# PDB_MH.net
KiCad netlist of a schematic drawn in EAGLE
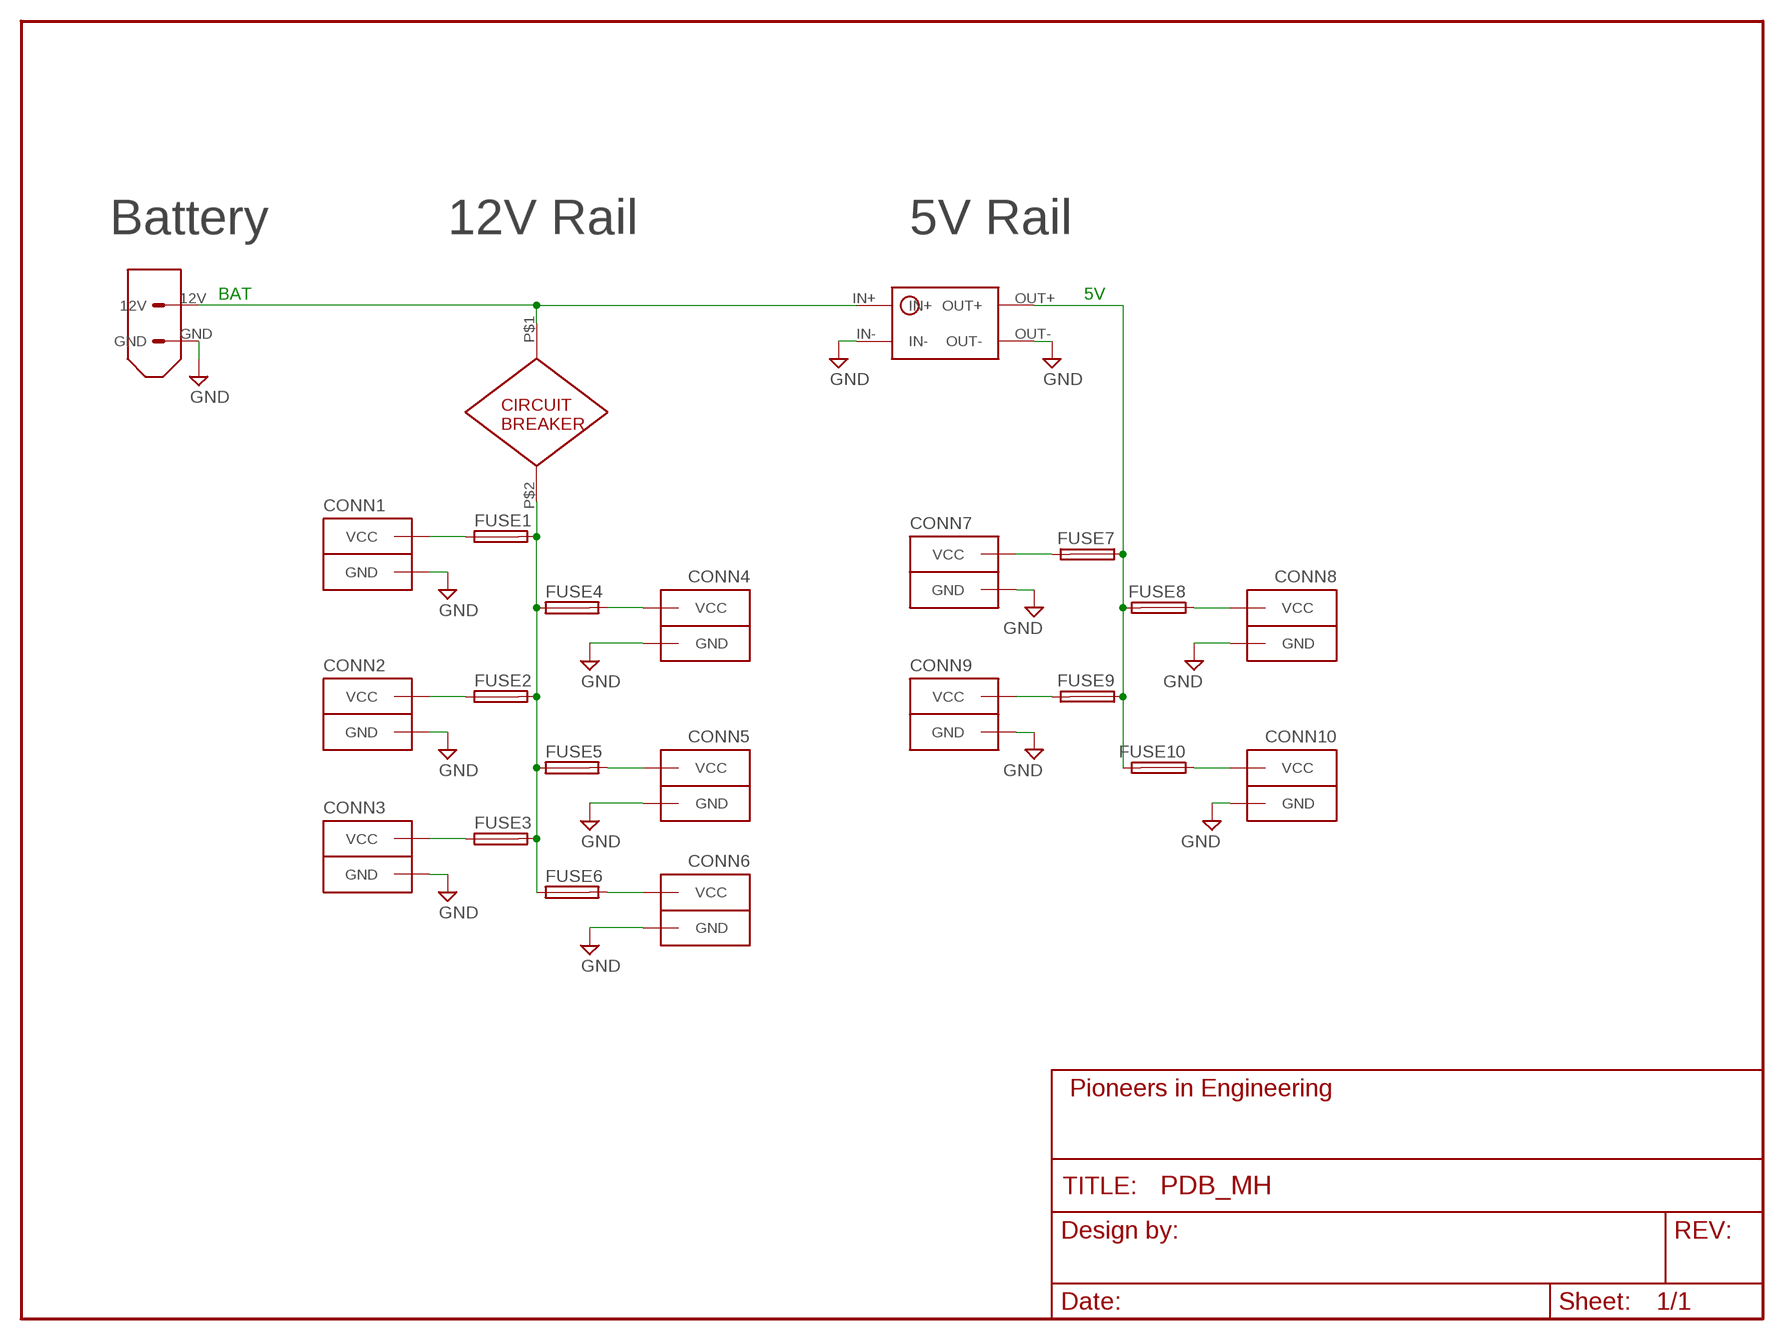
[diagram p0: schematic, sheet 1]

(export (version "E")
  (design (tool "Eeschema 10.0.6"))
  (components
    (comp (ref "CIRCUIT_BREAKER")
      (value "CIRC_BREAKER")
      (footprint "eagle-import:CIRC_BREAKER")
      (libsource (lib "eagle-import") (part "CIRC_BREAKER"))
    )
    (comp (ref "CONN1")
      (value "ANDERSONVERTICAL")
      (footprint "eagle-import:ANDERSON_VERTICAL")
      (libsource (lib "eagle-import") (part "ANDERSONVERTICAL"))
    )
    (comp (ref "CONN2")
      (value "ANDERSONVERTICAL")
      (footprint "eagle-import:ANDERSON_VERTICAL")
      (libsource (lib "eagle-import") (part "ANDERSONVERTICAL"))
    )
    (comp (ref "CONN3")
      (value "ANDERSONVERTICAL")
      (footprint "eagle-import:ANDERSON_VERTICAL")
      (libsource (lib "eagle-import") (part "ANDERSONVERTICAL"))
    )
    (comp (ref "CONN4")
      (value "ANDERSONVERTICAL")
      (footprint "eagle-import:ANDERSON_VERTICAL")
      (libsource (lib "eagle-import") (part "ANDERSONVERTICAL"))
    )
    (comp (ref "CONN5")
      (value "ANDERSONVERTICAL")
      (footprint "eagle-import:ANDERSON_VERTICAL")
      (libsource (lib "eagle-import") (part "ANDERSONVERTICAL"))
    )
    (comp (ref "CONN6")
      (value "ANDERSONVERTICAL")
      (footprint "eagle-import:ANDERSON_VERTICAL")
      (libsource (lib "eagle-import") (part "ANDERSONVERTICAL"))
    )
    (comp (ref "CONN7")
      (value "ANDERSONVERTICAL")
      (footprint "eagle-import:ANDERSON_VERTICAL")
      (libsource (lib "eagle-import") (part "ANDERSONVERTICAL"))
    )
    (comp (ref "CONN8")
      (value "ANDERSONVERTICAL")
      (footprint "eagle-import:ANDERSON_VERTICAL")
      (libsource (lib "eagle-import") (part "ANDERSONVERTICAL"))
    )
    (comp (ref "CONN9")
      (value "ANDERSONVERTICAL")
      (footprint "eagle-import:ANDERSON_VERTICAL")
      (libsource (lib "eagle-import") (part "ANDERSONVERTICAL"))
    )
    (comp (ref "CONN10")
      (value "ANDERSONVERTICAL")
      (footprint "eagle-import:ANDERSON_VERTICAL")
      (libsource (lib "eagle-import") (part "ANDERSONVERTICAL"))
    )
    (comp (ref "FUSE1")
      (value "FUSE_HOLDER_SMD")
      (footprint "eagle-import:FUSE_HOLDER_SMD")
      (libsource (lib "eagle-import") (part "FUSE_HOLDER_SMD"))
    )
    (comp (ref "FUSE2")
      (value "FUSE_HOLDER_SMD")
      (footprint "eagle-import:FUSE_HOLDER_SMD")
      (libsource (lib "eagle-import") (part "FUSE_HOLDER_SMD"))
    )
    (comp (ref "FUSE3")
      (value "FUSE_HOLDER_SMD")
      (footprint "eagle-import:FUSE_HOLDER_SMD")
      (libsource (lib "eagle-import") (part "FUSE_HOLDER_SMD"))
    )
    (comp (ref "FUSE4")
      (value "FUSE_HOLDER_SMD")
      (footprint "eagle-import:FUSE_HOLDER_SMD")
      (libsource (lib "eagle-import") (part "FUSE_HOLDER_SMD"))
    )
    (comp (ref "FUSE5")
      (value "FUSE_HOLDER_SMD")
      (footprint "eagle-import:FUSE_HOLDER_SMD")
      (libsource (lib "eagle-import") (part "FUSE_HOLDER_SMD"))
    )
    (comp (ref "FUSE6")
      (value "FUSE_HOLDER_SMD")
      (footprint "eagle-import:FUSE_HOLDER_SMD")
      (libsource (lib "eagle-import") (part "FUSE_HOLDER_SMD"))
    )
    (comp (ref "FUSE7")
      (value "FUSE_HOLDER_SMD")
      (footprint "eagle-import:FUSE_HOLDER_SMD")
      (libsource (lib "eagle-import") (part "FUSE_HOLDER_SMD"))
    )
    (comp (ref "FUSE8")
      (value "FUSE_HOLDER_SMD")
      (footprint "eagle-import:FUSE_HOLDER_SMD")
      (libsource (lib "eagle-import") (part "FUSE_HOLDER_SMD"))
    )
    (comp (ref "FUSE9")
      (value "FUSE_HOLDER_SMD")
      (footprint "eagle-import:FUSE_HOLDER_SMD")
      (libsource (lib "eagle-import") (part "FUSE_HOLDER_SMD"))
    )
    (comp (ref "FUSE10")
      (value "FUSE_HOLDER_SMD")
      (footprint "eagle-import:FUSE_HOLDER_SMD")
      (libsource (lib "eagle-import") (part "FUSE_HOLDER_SMD"))
    )
    (comp (ref "U$1")
      (value "XT60CONNECTOR")
      (footprint "eagle-import:XT60CONNECTOR")
      (fields (field (name "PARTNUMBER") "PRT-10474 "))
      (libsource (lib "eagle-import") (part "XT60CONNECTOR"))
    )
    (comp (ref "U$7")
      (value "BUCK_CONVERTER_5V")
      (footprint "eagle-import:BUCK_CONVERTER_5V")
      (libsource (lib "eagle-import") (part "BUCK_CONVERTER_5V"))
    )
  )
  (nets
    (net (code "1") (name "/5V") (class "Default")
      (node (ref "FUSE10") (pin "P$2_DOWN") (pinfunction "2_P$2_DOWN") (pintype "passive"))
      (node (ref "FUSE10") (pin "P$2_UP") (pinfunction "2_P$2_UP") (pintype "passive"))
      (node (ref "FUSE7") (pin "P$1_DOWN") (pinfunction "1_P$1_DOWN") (pintype "passive"))
      (node (ref "FUSE7") (pin "P$1_UP") (pinfunction "1_P$1_UP") (pintype "passive"))
      (node (ref "FUSE8") (pin "P$2_DOWN") (pinfunction "2_P$2_DOWN") (pintype "passive"))
      (node (ref "FUSE8") (pin "P$2_UP") (pinfunction "2_P$2_UP") (pintype "passive"))
      (node (ref "FUSE9") (pin "P$1_DOWN") (pinfunction "1_P$1_DOWN") (pintype "passive"))
      (node (ref "FUSE9") (pin "P$1_UP") (pinfunction "1_P$1_UP") (pintype "passive"))
      (node (ref "U$7") (pin "OUT+") (pinfunction "OUT+_OUT+") (pintype "bidirectional"))
    )
    (net (code "2") (name "/BAT") (class "Default")
      (node (ref "CIRCUIT_BREAKER") (pin "P$1") (pinfunction "P$1_P$1") (pintype "bidirectional"))
      (node (ref "U$1") (pin "12V") (pinfunction "12V_12V") (pintype "bidirectional"))
      (node (ref "U$7") (pin "IN+") (pinfunction "IN+_IN+") (pintype "bidirectional"))
    )
    (net (code "3") (name "GND") (class "Default")
      (node (ref "CONN1") (pin "PIN1") (pinfunction "GND_PIN1") (pintype "bidirectional"))
      (node (ref "CONN10") (pin "PIN1") (pinfunction "GND_PIN1") (pintype "bidirectional"))
      (node (ref "CONN2") (pin "PIN1") (pinfunction "GND_PIN1") (pintype "bidirectional"))
      (node (ref "CONN3") (pin "PIN1") (pinfunction "GND_PIN1") (pintype "bidirectional"))
      (node (ref "CONN4") (pin "PIN1") (pinfunction "GND_PIN1") (pintype "bidirectional"))
      (node (ref "CONN5") (pin "PIN1") (pinfunction "GND_PIN1") (pintype "bidirectional"))
      (node (ref "CONN6") (pin "PIN1") (pinfunction "GND_PIN1") (pintype "bidirectional"))
      (node (ref "CONN7") (pin "PIN1") (pinfunction "GND_PIN1") (pintype "bidirectional"))
      (node (ref "CONN8") (pin "PIN1") (pinfunction "GND_PIN1") (pintype "bidirectional"))
      (node (ref "CONN9") (pin "PIN1") (pinfunction "GND_PIN1") (pintype "bidirectional"))
      (node (ref "U$1") (pin "GND") (pinfunction "GND_GND") (pintype "bidirectional"))
      (node (ref "U$7") (pin "IN-") (pinfunction "IN-_IN-") (pintype "bidirectional"))
      (node (ref "U$7") (pin "OUT-") (pinfunction "OUT-_OUT-") (pintype "bidirectional"))
    )
    (net (code "4") (name "Net-(CIRCUIT_BREAKER-PadP$2)") (class "Default")
      (node (ref "CIRCUIT_BREAKER") (pin "P$2") (pinfunction "P$2_P$2") (pintype "bidirectional"))
      (node (ref "FUSE1") (pin "P$2_DOWN") (pinfunction "2_P$2_DOWN") (pintype "passive"))
      (node (ref "FUSE1") (pin "P$2_UP") (pinfunction "2_P$2_UP") (pintype "passive"))
      (node (ref "FUSE2") (pin "P$2_DOWN") (pinfunction "2_P$2_DOWN") (pintype "passive"))
      (node (ref "FUSE2") (pin "P$2_UP") (pinfunction "2_P$2_UP") (pintype "passive"))
      (node (ref "FUSE3") (pin "P$2_DOWN") (pinfunction "2_P$2_DOWN") (pintype "passive"))
      (node (ref "FUSE3") (pin "P$2_UP") (pinfunction "2_P$2_UP") (pintype "passive"))
      (node (ref "FUSE4") (pin "P$1_DOWN") (pinfunction "1_P$1_DOWN") (pintype "passive"))
      (node (ref "FUSE4") (pin "P$1_UP") (pinfunction "1_P$1_UP") (pintype "passive"))
      (node (ref "FUSE5") (pin "P$1_DOWN") (pinfunction "1_P$1_DOWN") (pintype "passive"))
      (node (ref "FUSE5") (pin "P$1_UP") (pinfunction "1_P$1_UP") (pintype "passive"))
      (node (ref "FUSE6") (pin "P$1_DOWN") (pinfunction "1_P$1_DOWN") (pintype "passive"))
      (node (ref "FUSE6") (pin "P$1_UP") (pinfunction "1_P$1_UP") (pintype "passive"))
    )
    (net (code "5") (name "Net-(CONN1-VCC)") (class "Default")
      (node (ref "CONN1") (pin "PIN2") (pinfunction "VCC_PIN2") (pintype "bidirectional"))
      (node (ref "FUSE1") (pin "P$1_DOWN") (pinfunction "1_P$1_DOWN") (pintype "passive"))
      (node (ref "FUSE1") (pin "P$1_UP") (pinfunction "1_P$1_UP") (pintype "passive"))
    )
    (net (code "6") (name "Net-(CONN2-VCC)") (class "Default")
      (node (ref "CONN2") (pin "PIN2") (pinfunction "VCC_PIN2") (pintype "bidirectional"))
      (node (ref "FUSE2") (pin "P$1_DOWN") (pinfunction "1_P$1_DOWN") (pintype "passive"))
      (node (ref "FUSE2") (pin "P$1_UP") (pinfunction "1_P$1_UP") (pintype "passive"))
    )
    (net (code "7") (name "Net-(CONN3-VCC)") (class "Default")
      (node (ref "CONN3") (pin "PIN2") (pinfunction "VCC_PIN2") (pintype "bidirectional"))
      (node (ref "FUSE3") (pin "P$1_DOWN") (pinfunction "1_P$1_DOWN") (pintype "passive"))
      (node (ref "FUSE3") (pin "P$1_UP") (pinfunction "1_P$1_UP") (pintype "passive"))
    )
    (net (code "8") (name "Net-(CONN4-VCC)") (class "Default")
      (node (ref "CONN4") (pin "PIN2") (pinfunction "VCC_PIN2") (pintype "bidirectional"))
      (node (ref "FUSE4") (pin "P$2_DOWN") (pinfunction "2_P$2_DOWN") (pintype "passive"))
      (node (ref "FUSE4") (pin "P$2_UP") (pinfunction "2_P$2_UP") (pintype "passive"))
    )
    (net (code "9") (name "Net-(CONN5-VCC)") (class "Default")
      (node (ref "CONN5") (pin "PIN2") (pinfunction "VCC_PIN2") (pintype "bidirectional"))
      (node (ref "FUSE5") (pin "P$2_DOWN") (pinfunction "2_P$2_DOWN") (pintype "passive"))
      (node (ref "FUSE5") (pin "P$2_UP") (pinfunction "2_P$2_UP") (pintype "passive"))
    )
    (net (code "10") (name "Net-(CONN6-VCC)") (class "Default")
      (node (ref "CONN6") (pin "PIN2") (pinfunction "VCC_PIN2") (pintype "bidirectional"))
      (node (ref "FUSE6") (pin "P$2_DOWN") (pinfunction "2_P$2_DOWN") (pintype "passive"))
      (node (ref "FUSE6") (pin "P$2_UP") (pinfunction "2_P$2_UP") (pintype "passive"))
    )
    (net (code "11") (name "Net-(CONN7-VCC)") (class "Default")
      (node (ref "CONN7") (pin "PIN2") (pinfunction "VCC_PIN2") (pintype "bidirectional"))
      (node (ref "FUSE7") (pin "P$2_DOWN") (pinfunction "2_P$2_DOWN") (pintype "passive"))
      (node (ref "FUSE7") (pin "P$2_UP") (pinfunction "2_P$2_UP") (pintype "passive"))
    )
    (net (code "12") (name "Net-(CONN8-VCC)") (class "Default")
      (node (ref "CONN8") (pin "PIN2") (pinfunction "VCC_PIN2") (pintype "bidirectional"))
      (node (ref "FUSE8") (pin "P$1_DOWN") (pinfunction "1_P$1_DOWN") (pintype "passive"))
      (node (ref "FUSE8") (pin "P$1_UP") (pinfunction "1_P$1_UP") (pintype "passive"))
    )
    (net (code "13") (name "Net-(CONN9-VCC)") (class "Default")
      (node (ref "CONN9") (pin "PIN2") (pinfunction "VCC_PIN2") (pintype "bidirectional"))
      (node (ref "FUSE9") (pin "P$2_DOWN") (pinfunction "2_P$2_DOWN") (pintype "passive"))
      (node (ref "FUSE9") (pin "P$2_UP") (pinfunction "2_P$2_UP") (pintype "passive"))
    )
    (net (code "14") (name "Net-(CONN10-VCC)") (class "Default")
      (node (ref "CONN10") (pin "PIN2") (pinfunction "VCC_PIN2") (pintype "bidirectional"))
      (node (ref "FUSE10") (pin "P$1_DOWN") (pinfunction "1_P$1_DOWN") (pintype "passive"))
      (node (ref "FUSE10") (pin "P$1_UP") (pinfunction "1_P$1_UP") (pintype "passive"))
    )
  )
)
